# ReuseBlock_5VBuck_MP2236_module_2024-12-.net
KiCad netlist of a schematic drawn in EasyEDA Pro
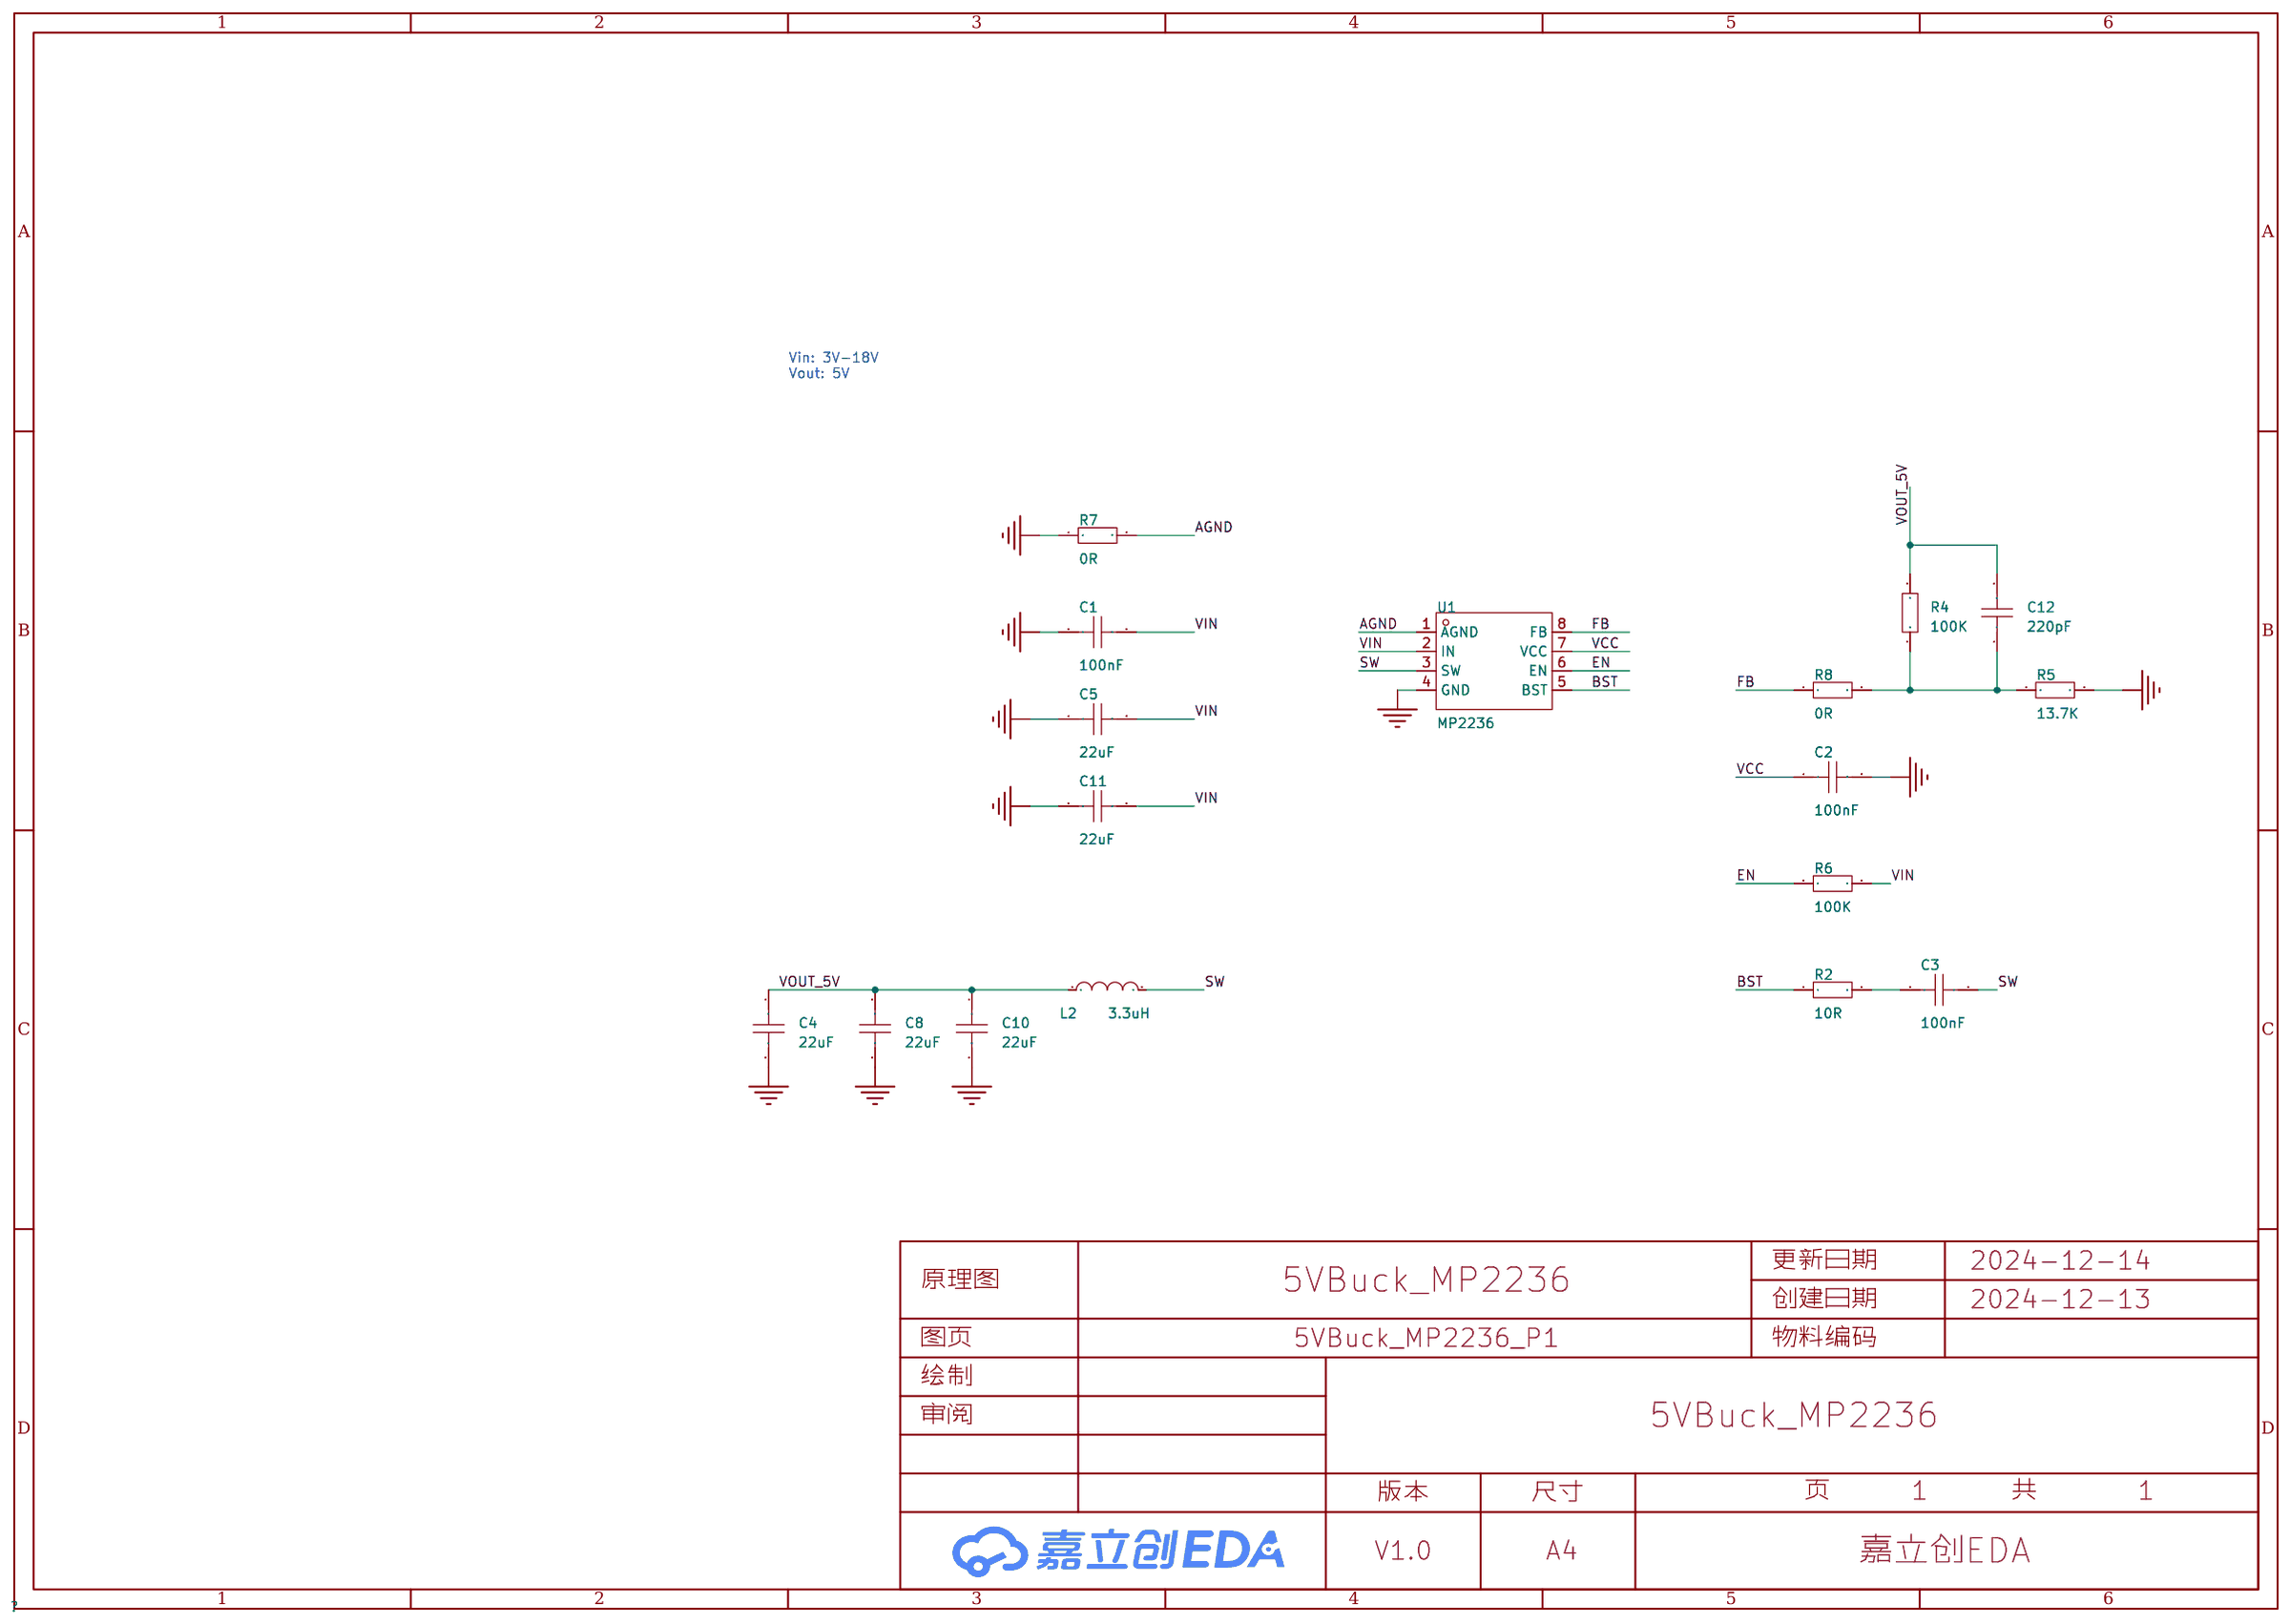
[diagram p0: schematic sheet]

(export (version "E")
  (design (tool "Eeschema 10.0.6"))
  (components
    (comp (ref "C1")
      (value "100nF")
      (footprint "easyedapro:C0805")
      (libsource (lib "easyedapro") (part "CapAcitance"))
    )
    (comp (ref "C2")
      (value "100nF")
      (footprint "easyedapro:C0805")
      (libsource (lib "easyedapro") (part "CapAcitance"))
    )
    (comp (ref "C3")
      (value "100nF")
      (footprint "easyedapro:C0805")
      (libsource (lib "easyedapro") (part "CapAcitance"))
    )
    (comp (ref "C4")
      (value "22uF")
      (footprint "easyedapro:C0805")
      (libsource (lib "easyedapro") (part "CapAcitance"))
    )
    (comp (ref "C5")
      (value "22uF")
      (footprint "easyedapro:C0805")
      (libsource (lib "easyedapro") (part "CapAcitance"))
    )
    (comp (ref "C8")
      (value "22uF")
      (footprint "easyedapro:C0805")
      (libsource (lib "easyedapro") (part "CapAcitance"))
    )
    (comp (ref "C10")
      (value "22uF")
      (footprint "easyedapro:C0805")
      (libsource (lib "easyedapro") (part "CapAcitance"))
    )
    (comp (ref "C11")
      (value "22uF")
      (footprint "easyedapro:C0805")
      (libsource (lib "easyedapro") (part "CapAcitance"))
    )
    (comp (ref "C12")
      (value "220pF")
      (footprint "easyedapro:C0805")
      (libsource (lib "easyedapro") (part "CapAcitance"))
    )
    (comp (ref "L2")
      (value "3.3uH")
      (footprint "easyedapro:IND-SMD_L7.1-W6.6_MJC-0603T")
      (description "电感值:5.6uH;精度:±20%;额定电流:5.5A;饱和电流(Isat):7A;类型:一体成型电感;")
      (fields
        (field (name "Manufacturer Part") "CXP0630-5R6M-AG(5.6uh)")
        (field (name "Manufacturer") "DMBJ(振宝佳)")
      )
      (libsource (lib "easyedapro") (part "CXP0630-5R6M-AG(5.6UH)"))
    )
    (comp (ref "R2") (value "10R") (footprint "easyedapro:R0805") (libsource (lib "easyedapro") (part "电阻")))
    (comp (ref "R4") (value "100K") (footprint "easyedapro:R0805") (libsource (lib "easyedapro") (part "电阻")))
    (comp (ref "R5")
      (value "13.7K")
      (footprint "easyedapro:R0805")
      (libsource (lib "easyedapro") (part "电阻"))
    )
    (comp (ref "R6") (value "100K") (footprint "easyedapro:R0805") (libsource (lib "easyedapro") (part "电阻")))
    (comp (ref "R7") (value "0R") (footprint "easyedapro:R0805") (libsource (lib "easyedapro") (part "电阻")))
    (comp (ref "R8") (value "0R") (footprint "easyedapro:R0805") (libsource (lib "easyedapro") (part "电阻")))
    (comp (ref "U1")
      (value "MP2236")
      (footprint "easyedapro:SOT-23-8_L3.0-W1.7-P0.65-LS2.8-BL")
      (libsource (lib "easyedapro") (part "MP2236"))
    )
  )
  (nets
    (net (code "1") (name "/AGND") (class "Default")
      (node (ref "R7") (pin "2") (pinfunction "2_2") (pintype "input"))
      (node (ref "U1") (pin "1") (pinfunction "AGND_1") (pintype "unspecified"))
    )
    (net (code "2") (name "/BST") (class "Default")
      (node (ref "R2") (pin "1") (pinfunction "1_1") (pintype "input"))
      (node (ref "U1") (pin "5") (pinfunction "BST_5") (pintype "unspecified"))
    )
    (net (code "3") (name "/EN") (class "Default")
      (node (ref "R6") (pin "2") (pinfunction "2_2") (pintype "input"))
      (node (ref "U1") (pin "6") (pinfunction "EN_6") (pintype "unspecified"))
    )
    (net (code "4") (name "/FB") (class "Default")
      (node (ref "R8") (pin "1") (pinfunction "1_1") (pintype "input"))
      (node (ref "U1") (pin "8") (pinfunction "FB_8") (pintype "unspecified"))
    )
    (net (code "5") (name "/SW") (class "Default")
      (node (ref "C3") (pin "2") (pinfunction "2_2") (pintype "input"))
      (node (ref "L2") (pin "2") (pinfunction "2_2") (pintype "unspecified"))
      (node (ref "U1") (pin "3") (pinfunction "SW_3") (pintype "unspecified"))
    )
    (net (code "6") (name "/VCC") (class "Default")
      (node (ref "C2") (pin "1") (pinfunction "1_1") (pintype "input"))
      (node (ref "U1") (pin "7") (pinfunction "VCC_7") (pintype "unspecified"))
    )
    (net (code "7") (name "/VIN") (class "Default")
      (node (ref "C1") (pin "2") (pinfunction "2_2") (pintype "input"))
      (node (ref "C11") (pin "2") (pinfunction "2_2") (pintype "input"))
      (node (ref "C5") (pin "2") (pinfunction "2_2") (pintype "input"))
      (node (ref "R6") (pin "1") (pinfunction "1_1") (pintype "input"))
      (node (ref "U1") (pin "2") (pinfunction "IN_2") (pintype "unspecified"))
    )
    (net (code "8") (name "/VOUT_5V") (class "Default")
      (node (ref "C10") (pin "1") (pinfunction "1_1") (pintype "input"))
      (node (ref "C12") (pin "2") (pinfunction "2_2") (pintype "input"))
      (node (ref "C4") (pin "1") (pinfunction "1_1") (pintype "input"))
      (node (ref "C8") (pin "1") (pinfunction "1_1") (pintype "input"))
      (node (ref "L2") (pin "1") (pinfunction "1_1") (pintype "unspecified"))
      (node (ref "R4") (pin "2") (pinfunction "2_2") (pintype "input"))
    )
    (net (code "9") (name "GND") (class "Default")
      (node (ref "C1") (pin "1") (pinfunction "1_1") (pintype "input"))
      (node (ref "C10") (pin "2") (pinfunction "2_2") (pintype "input"))
      (node (ref "C11") (pin "1") (pinfunction "1_1") (pintype "input"))
      (node (ref "C2") (pin "2") (pinfunction "2_2") (pintype "input"))
      (node (ref "C4") (pin "2") (pinfunction "2_2") (pintype "input"))
      (node (ref "C5") (pin "1") (pinfunction "1_1") (pintype "input"))
      (node (ref "C8") (pin "2") (pinfunction "2_2") (pintype "input"))
      (node (ref "R5") (pin "2") (pinfunction "2_2") (pintype "input"))
      (node (ref "R7") (pin "1") (pinfunction "1_1") (pintype "input"))
      (node (ref "U1") (pin "4") (pinfunction "GND_4") (pintype "unspecified"))
    )
    (net (code "10") (name "Net-(C3-Pad1)") (class "Default")
      (node (ref "C3") (pin "1") (pinfunction "1_1") (pintype "input"))
      (node (ref "R2") (pin "2") (pinfunction "2_2") (pintype "input"))
    )
    (net (code "11") (name "Net-(C12-Pad1)") (class "Default")
      (node (ref "C12") (pin "1") (pinfunction "1_1") (pintype "input"))
      (node (ref "R4") (pin "1") (pinfunction "1_1") (pintype "input"))
      (node (ref "R5") (pin "1") (pinfunction "1_1") (pintype "input"))
      (node (ref "R8") (pin "2") (pinfunction "2_2") (pintype "input"))
    )
  )
)
